# Power_delivery.net
KiCad netlist of a schematic drawn in Altium Designer
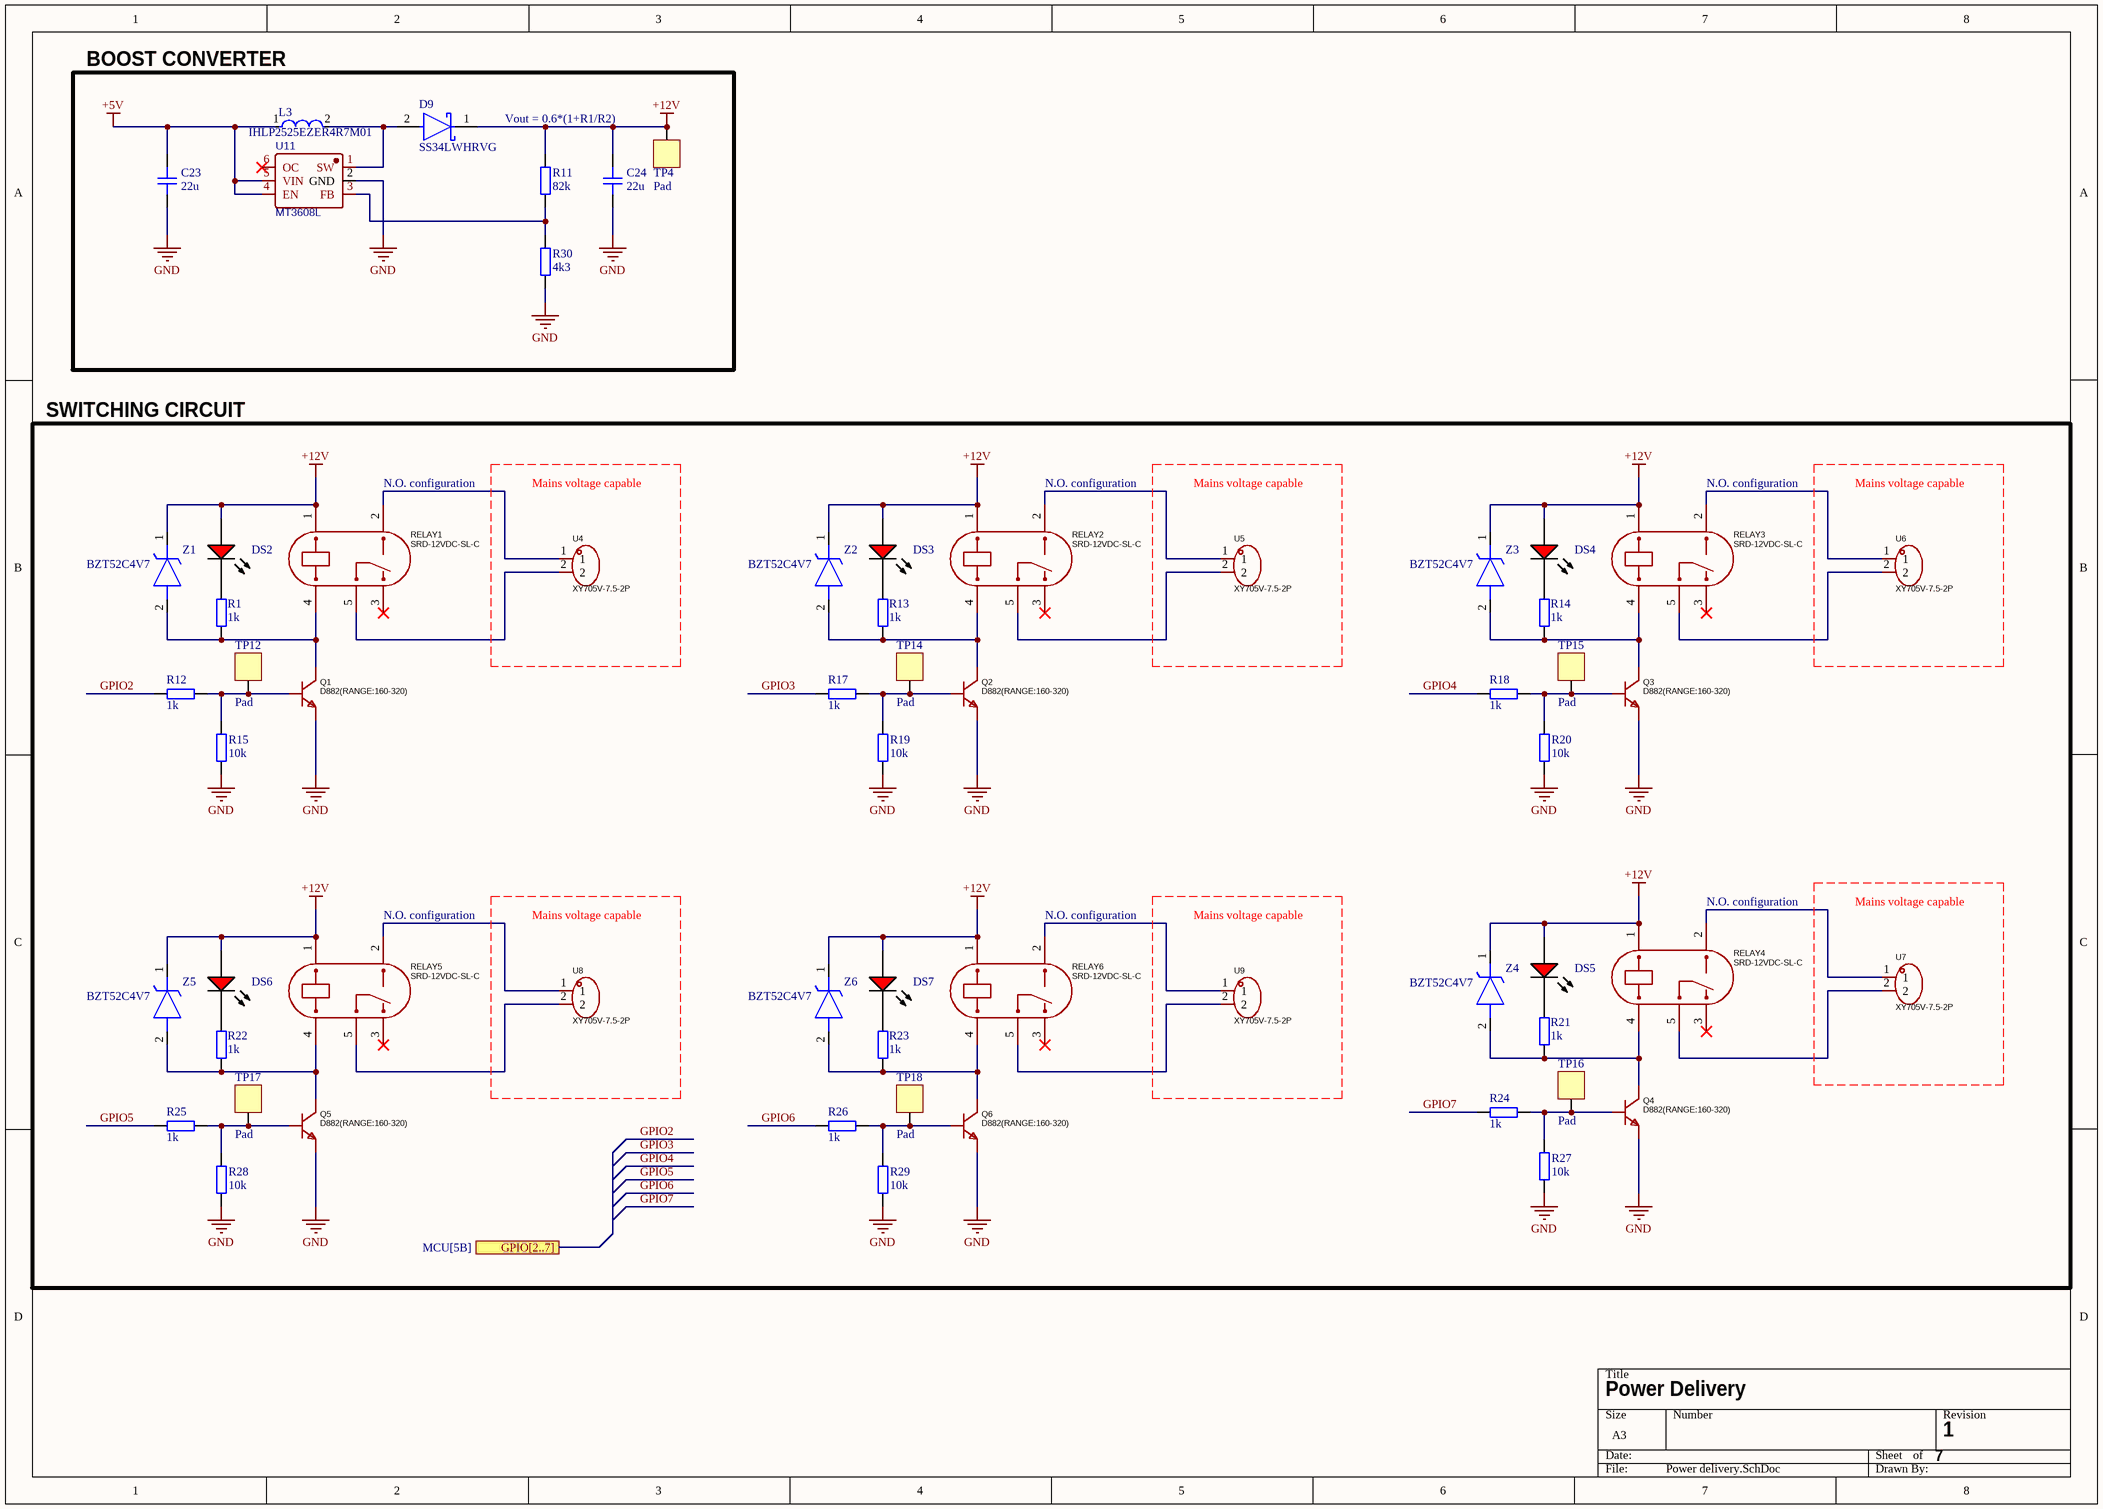
[diagram p0: Power delivery.SchDoc]

(export (version "E")
  (design (tool "Eeschema 10.0.6"))
  (components
    (comp (ref "C23")
      (value "GRM158R61A226ME15D")
      (footprint "CAP_0402")
      (description "Capacitor SMD 0402")
      (fields (field (name "RATING") "22u"))
      (libsource (lib "Schematic-Lib-PhilsLab") (part "CAP_0402"))
    )
    (comp (ref "C24")
      (value "GRM158R61A226ME15D")
      (footprint "CAP_0402")
      (description "Capacitor SMD 0402")
      (fields (field (name "RATING") "22u"))
      (libsource (lib "Schematic-Lib-PhilsLab") (part "CAP_0402"))
    )
    (comp (ref "D9")
      (value "SS34LWHRVG")
      (footprint "FP-SS34LWH-MFG")
      (description "DIODE SCHOTTKY 40V 3A SOD123W")
      (libsource (lib "Altium Content Vault") (part "1d6ec82d83fb6aee721767c19dac4b9"))
    )
    (comp (ref "DS2")
      (value "LTST-C170KRKT")
      (footprint "LTST-C170KRKT_V")
      (description "LED Red, 75 mW, 54 mcd, -55 to 85 degC, 2-Pin SMD, RoHS, Tape and Reel")
      (fields (field (name "MANUFACTURER") "Lite-On"))
      (libsource (lib "Altium Content Vault") (part "LED-RED-AK-2"))
    )
    (comp (ref "DS3")
      (value "LTST-C170KRKT")
      (footprint "LTST-C170KRKT_V")
      (description "LED Red, 75 mW, 54 mcd, -55 to 85 degC, 2-Pin SMD, RoHS, Tape and Reel")
      (fields (field (name "MANUFACTURER") "Lite-On"))
      (libsource (lib "Altium Content Vault") (part "LED-RED-AK-2"))
    )
    (comp (ref "DS4")
      (value "LTST-C170KRKT")
      (footprint "LTST-C170KRKT_V")
      (description "LED Red, 75 mW, 54 mcd, -55 to 85 degC, 2-Pin SMD, RoHS, Tape and Reel")
      (fields (field (name "MANUFACTURER") "Lite-On"))
      (libsource (lib "Altium Content Vault") (part "LED-RED-AK-2"))
    )
    (comp (ref "DS5")
      (value "LTST-C170KRKT")
      (footprint "LTST-C170KRKT_V")
      (description "LED Red, 75 mW, 54 mcd, -55 to 85 degC, 2-Pin SMD, RoHS, Tape and Reel")
      (fields (field (name "MANUFACTURER") "Lite-On"))
      (libsource (lib "Altium Content Vault") (part "LED-RED-AK-2"))
    )
    (comp (ref "DS6")
      (value "LTST-C170KRKT")
      (footprint "LTST-C170KRKT_V")
      (description "LED Red, 75 mW, 54 mcd, -55 to 85 degC, 2-Pin SMD, RoHS, Tape and Reel")
      (fields (field (name "MANUFACTURER") "Lite-On"))
      (libsource (lib "Altium Content Vault") (part "LED-RED-AK-2"))
    )
    (comp (ref "DS7")
      (value "LTST-C170KRKT")
      (footprint "LTST-C170KRKT_V")
      (description "LED Red, 75 mW, 54 mcd, -55 to 85 degC, 2-Pin SMD, RoHS, Tape and Reel")
      (fields (field (name "MANUFACTURER") "Lite-On"))
      (libsource (lib "Altium Content Vault") (part "LED-RED-AK-2"))
    )
    (comp (ref "L3")
      (value "IHLP2525EZER4R7M01")
      (footprint "FP-IHLP-2525EZ-FP_2_413x3-MFG")
      (description "Commercial Inductors, High Saturation Series 4.7uH 6.5A 30.3mΩ 20%")
      (fields (field (name "TOLERANCE") "20%"))
      (libsource (lib "Altium Content Vault") (part "725321dda6339637d4d059423bc1c3c"))
    )
    (comp (ref "Q1")
      (value "D882(RANGE:160-320)")
      (footprint "SOT-89-3_L4.5-W2.5-P1.50-LS4.2-BR")
      (fields (field (name "MANUFACTURER") "CJ(江苏长电/长晶)"))
      (libsource (lib "JLCPCB_parts_library") (part "D882(RANGE{colon}160-320)_C9634"))
    )
    (comp (ref "Q2")
      (value "D882(RANGE:160-320)")
      (footprint "SOT-89-3_L4.5-W2.5-P1.50-LS4.2-BR")
      (fields (field (name "MANUFACTURER") "CJ(江苏长电/长晶)"))
      (libsource (lib "JLCPCB_parts_library") (part "D882(RANGE{colon}160-320)_C9634"))
    )
    (comp (ref "Q3")
      (value "D882(RANGE:160-320)")
      (footprint "SOT-89-3_L4.5-W2.5-P1.50-LS4.2-BR")
      (fields (field (name "MANUFACTURER") "CJ(江苏长电/长晶)"))
      (libsource (lib "JLCPCB_parts_library") (part "D882(RANGE{colon}160-320)_C9634"))
    )
    (comp (ref "Q4")
      (value "D882(RANGE:160-320)")
      (footprint "SOT-89-3_L4.5-W2.5-P1.50-LS4.2-BR")
      (fields (field (name "MANUFACTURER") "CJ(江苏长电/长晶)"))
      (libsource (lib "JLCPCB_parts_library") (part "D882(RANGE{colon}160-320)_C9634"))
    )
    (comp (ref "Q5")
      (value "D882(RANGE:160-320)")
      (footprint "SOT-89-3_L4.5-W2.5-P1.50-LS4.2-BR")
      (fields (field (name "MANUFACTURER") "CJ(江苏长电/长晶)"))
      (libsource (lib "JLCPCB_parts_library") (part "D882(RANGE{colon}160-320)_C9634"))
    )
    (comp (ref "Q6")
      (value "D882(RANGE:160-320)")
      (footprint "SOT-89-3_L4.5-W2.5-P1.50-LS4.2-BR")
      (fields (field (name "MANUFACTURER") "CJ(江苏长电/长晶)"))
      (libsource (lib "JLCPCB_parts_library") (part "D882(RANGE{colon}160-320)_C9634"))
    )
    (comp (ref "R1")
      (value "1k")
      (footprint "RES_1206")
      (description "Resistor SMD 1206 1k 0.5W")
      (fields (field (name "Comment") "RC1206FR-7W1KL"))
      (libsource (lib "Schematic-Lib-PhilsLab") (part "RES_1206"))
    )
    (comp (ref "R11")
      (value "82k")
      (footprint "RES_0402")
      (description "Resistor SMD 0402")
      (fields (field (name "Comment") "0402WGF8202TCE"))
      (libsource (lib "Schematic-Lib-PhilsLab") (part "RES_0402"))
    )
    (comp (ref "R12")
      (value "1k")
      (footprint "RES_1206")
      (description "Resistor SMD 1206 1k 0.5W")
      (fields (field (name "Comment") "RC1206FR-7W1KL"))
      (libsource (lib "Schematic-Lib-PhilsLab") (part "RES_1206"))
    )
    (comp (ref "R13")
      (value "1k")
      (footprint "RES_1206")
      (description "Resistor SMD 1206 1k 0.5W")
      (fields (field (name "Comment") "RC1206FR-7W1KL"))
      (libsource (lib "Schematic-Lib-PhilsLab") (part "RES_1206"))
    )
    (comp (ref "R14")
      (value "1k")
      (footprint "RES_1206")
      (description "Resistor SMD 1206 1k 0.5W")
      (fields (field (name "Comment") "RC1206FR-7W1KL"))
      (libsource (lib "Schematic-Lib-PhilsLab") (part "RES_1206"))
    )
    (comp (ref "R15")
      (value "10k")
      (footprint "RES_1206")
      (description "Resistor SMD 1206 10k 0.25W")
      (fields (field (name "Comment") "1206W4F1002T5E"))
      (libsource (lib "Schematic-Lib-PhilsLab") (part "RES_1206"))
    )
    (comp (ref "R17")
      (value "1k")
      (footprint "RES_1206")
      (description "Resistor SMD 1206 1k 0.5W")
      (fields (field (name "Comment") "RC1206FR-7W1KL"))
      (libsource (lib "Schematic-Lib-PhilsLab") (part "RES_1206"))
    )
    (comp (ref "R18")
      (value "1k")
      (footprint "RES_1206")
      (description "Resistor SMD 1206 1k 0.5W")
      (fields (field (name "Comment") "RC1206FR-7W1KL"))
      (libsource (lib "Schematic-Lib-PhilsLab") (part "RES_1206"))
    )
    (comp (ref "R19")
      (value "10k")
      (footprint "RES_1206")
      (description "Resistor SMD 1206 10k 0.25W")
      (fields (field (name "Comment") "1206W4F1002T5E"))
      (libsource (lib "Schematic-Lib-PhilsLab") (part "RES_1206"))
    )
    (comp (ref "R20")
      (value "10k")
      (footprint "RES_1206")
      (description "Resistor SMD 1206 10k 0.25W")
      (fields (field (name "Comment") "1206W4F1002T5E"))
      (libsource (lib "Schematic-Lib-PhilsLab") (part "RES_1206"))
    )
    (comp (ref "R21")
      (value "1k")
      (footprint "RES_1206")
      (description "Resistor SMD 1206 1k 0.5W")
      (fields (field (name "Comment") "RC1206FR-7W1KL"))
      (libsource (lib "Schematic-Lib-PhilsLab") (part "RES_1206"))
    )
    (comp (ref "R22")
      (value "1k")
      (footprint "RES_1206")
      (description "Resistor SMD 1206 1k 0.5W")
      (fields (field (name "Comment") "RC1206FR-7W1KL"))
      (libsource (lib "Schematic-Lib-PhilsLab") (part "RES_1206"))
    )
    (comp (ref "R23")
      (value "1k")
      (footprint "RES_1206")
      (description "Resistor SMD 1206 1k 0.5W")
      (fields (field (name "Comment") "RC1206FR-7W1KL"))
      (libsource (lib "Schematic-Lib-PhilsLab") (part "RES_1206"))
    )
    (comp (ref "R24")
      (value "1k")
      (footprint "RES_1206")
      (description "Resistor SMD 1206 1k 0.5W")
      (fields (field (name "Comment") "RC1206FR-7W1KL"))
      (libsource (lib "Schematic-Lib-PhilsLab") (part "RES_1206"))
    )
    (comp (ref "R25")
      (value "1k")
      (footprint "RES_1206")
      (description "Resistor SMD 1206 1k 0.5W")
      (fields (field (name "Comment") "RC1206FR-7W1KL"))
      (libsource (lib "Schematic-Lib-PhilsLab") (part "RES_1206"))
    )
    (comp (ref "R26")
      (value "1k")
      (footprint "RES_1206")
      (description "Resistor SMD 1206 1k 0.5W")
      (fields (field (name "Comment") "RC1206FR-7W1KL"))
      (libsource (lib "Schematic-Lib-PhilsLab") (part "RES_1206"))
    )
    (comp (ref "R27")
      (value "10k")
      (footprint "RES_1206")
      (description "Resistor SMD 1206 10k 0.25W")
      (fields (field (name "Comment") "1206W4F1002T5E"))
      (libsource (lib "Schematic-Lib-PhilsLab") (part "RES_1206"))
    )
    (comp (ref "R28")
      (value "10k")
      (footprint "RES_1206")
      (description "Resistor SMD 1206 10k 0.25W")
      (fields (field (name "Comment") "1206W4F1002T5E"))
      (libsource (lib "Schematic-Lib-PhilsLab") (part "RES_1206"))
    )
    (comp (ref "R29")
      (value "10k")
      (footprint "RES_1206")
      (description "Resistor SMD 1206 10k 0.25W")
      (fields (field (name "Comment") "1206W4F1002T5E"))
      (libsource (lib "Schematic-Lib-PhilsLab") (part "RES_1206"))
    )
    (comp (ref "R30")
      (value "4k3")
      (footprint "RES_0402")
      (description "Resistor SMD 0402")
      (fields (field (name "Comment") "RC0402FR-074K3L"))
      (libsource (lib "Schematic-Lib-PhilsLab") (part "RES_0402"))
    )
    (comp (ref "RELAY1")
      (value "SRD-12VDC-SL-C")
      (footprint "RELAY-TH_SRD-XXVDC-XL-C")
      (fields (field (name "MANUFACTURER") "松乐"))
      (libsource (lib "JLCPCB_parts_library") (part "SRD-12VDC-SL-C"))
    )
    (comp (ref "RELAY2")
      (value "SRD-12VDC-SL-C")
      (footprint "RELAY-TH_SRD-XXVDC-XL-C")
      (fields (field (name "MANUFACTURER") "松乐"))
      (libsource (lib "JLCPCB_parts_library") (part "SRD-12VDC-SL-C"))
    )
    (comp (ref "RELAY3")
      (value "SRD-12VDC-SL-C")
      (footprint "RELAY-TH_SRD-XXVDC-XL-C")
      (fields (field (name "MANUFACTURER") "松乐"))
      (libsource (lib "JLCPCB_parts_library") (part "SRD-12VDC-SL-C"))
    )
    (comp (ref "RELAY4")
      (value "SRD-12VDC-SL-C")
      (footprint "RELAY-TH_SRD-XXVDC-XL-C")
      (fields (field (name "MANUFACTURER") "松乐"))
      (libsource (lib "JLCPCB_parts_library") (part "SRD-12VDC-SL-C"))
    )
    (comp (ref "RELAY5")
      (value "SRD-12VDC-SL-C")
      (footprint "RELAY-TH_SRD-XXVDC-XL-C")
      (fields (field (name "MANUFACTURER") "松乐"))
      (libsource (lib "JLCPCB_parts_library") (part "SRD-12VDC-SL-C"))
    )
    (comp (ref "RELAY6")
      (value "SRD-12VDC-SL-C")
      (footprint "RELAY-TH_SRD-XXVDC-XL-C")
      (fields (field (name "MANUFACTURER") "松乐"))
      (libsource (lib "JLCPCB_parts_library") (part "SRD-12VDC-SL-C"))
    )
    (comp (ref "TP4")
      (value "Pad")
      (footprint "PAD_SQ_2MM")
      (description "Test Point Square 2mm")
      (libsource (lib "") (part "PAD_SQ_2MM_1"))
    )
    (comp (ref "TP12")
      (value "Pad")
      (footprint "PAD_SQ_2MM")
      (description "Test Point Square 2mm")
      (libsource (lib "Schematic-Lib-PhilsLab") (part "PAD_SQ_2MM"))
    )
    (comp (ref "TP14")
      (value "Pad")
      (footprint "PAD_SQ_2MM")
      (description "Test Point Square 2mm")
      (libsource (lib "Schematic-Lib-PhilsLab") (part "PAD_SQ_2MM"))
    )
    (comp (ref "TP15")
      (value "Pad")
      (footprint "PAD_SQ_2MM")
      (description "Test Point Square 2mm")
      (libsource (lib "Schematic-Lib-PhilsLab") (part "PAD_SQ_2MM"))
    )
    (comp (ref "TP16")
      (value "Pad")
      (footprint "PAD_SQ_2MM")
      (description "Test Point Square 2mm")
      (libsource (lib "Schematic-Lib-PhilsLab") (part "PAD_SQ_2MM"))
    )
    (comp (ref "TP17")
      (value "Pad")
      (footprint "PAD_SQ_2MM")
      (description "Test Point Square 2mm")
      (libsource (lib "Schematic-Lib-PhilsLab") (part "PAD_SQ_2MM"))
    )
    (comp (ref "TP18")
      (value "Pad")
      (footprint "PAD_SQ_2MM")
      (description "Test Point Square 2mm")
      (libsource (lib "Schematic-Lib-PhilsLab") (part "PAD_SQ_2MM"))
    )
    (comp (ref "U4")
      (value "XY705V-7.5-2P")
      (footprint "CONN-TH_XY705V-7.5-2P")
      (fields (field (name "MANUFACTURER") "XINLAIYA(新莱亚)"))
      (libsource (lib "JLCPCB_parts_library") (part "XY705V-7.5-2P"))
    )
    (comp (ref "U5")
      (value "XY705V-7.5-2P")
      (footprint "CONN-TH_XY705V-7.5-2P")
      (fields (field (name "MANUFACTURER") "XINLAIYA(新莱亚)"))
      (libsource (lib "JLCPCB_parts_library") (part "XY705V-7.5-2P"))
    )
    (comp (ref "U6")
      (value "XY705V-7.5-2P")
      (footprint "CONN-TH_XY705V-7.5-2P")
      (fields (field (name "MANUFACTURER") "XINLAIYA(新莱亚)"))
      (libsource (lib "JLCPCB_parts_library") (part "XY705V-7.5-2P"))
    )
    (comp (ref "U7")
      (value "XY705V-7.5-2P")
      (footprint "CONN-TH_XY705V-7.5-2P")
      (fields (field (name "MANUFACTURER") "XINLAIYA(新莱亚)"))
      (libsource (lib "JLCPCB_parts_library") (part "XY705V-7.5-2P"))
    )
    (comp (ref "U8")
      (value "XY705V-7.5-2P")
      (footprint "CONN-TH_XY705V-7.5-2P")
      (fields (field (name "MANUFACTURER") "XINLAIYA(新莱亚)"))
      (libsource (lib "JLCPCB_parts_library") (part "XY705V-7.5-2P"))
    )
    (comp (ref "U9")
      (value "XY705V-7.5-2P")
      (footprint "CONN-TH_XY705V-7.5-2P")
      (fields (field (name "MANUFACTURER") "XINLAIYA(新莱亚)"))
      (libsource (lib "JLCPCB_parts_library") (part "XY705V-7.5-2P"))
    )
    (comp (ref "U11")
      (value "MT3608L")
      (footprint "SOT-23-6_L2.9-W1.6-P0.95-LS2.8-BL_3")
      (fields (field (name "MANUFACTURER") "西安航天民芯") (field (name "CONTRIBUTOR") "LCSC"))
      (libsource (lib "JLCPCB_parts_library") (part "MT3608L"))
    )
    (comp (ref "Z1")
      (value "BZT52C4V7")
      (footprint "JLCPCB_parts_library:BZT52C4V7")
      (description "Zener Diode")
      (fields (field (name "MOUSER PART NUMBER") "637-BZT52C4V7"))
      (libsource (lib "JLCPCB_parts_library") (part "BZT52C4V7"))
    )
    (comp (ref "Z2")
      (value "BZT52C4V7")
      (footprint "JLCPCB_parts_library:BZT52C4V7")
      (description "Zener Diode")
      (fields (field (name "MOUSER PART NUMBER") "637-BZT52C4V7"))
      (libsource (lib "JLCPCB_parts_library") (part "BZT52C4V7"))
    )
    (comp (ref "Z3")
      (value "BZT52C4V7")
      (footprint "JLCPCB_parts_library:BZT52C4V7")
      (description "Zener Diode")
      (fields (field (name "MOUSER PART NUMBER") "637-BZT52C4V7"))
      (libsource (lib "JLCPCB_parts_library") (part "BZT52C4V7"))
    )
    (comp (ref "Z4")
      (value "BZT52C4V7")
      (footprint "JLCPCB_parts_library:BZT52C4V7")
      (description "Zener Diode")
      (fields (field (name "MOUSER PART NUMBER") "637-BZT52C4V7"))
      (libsource (lib "JLCPCB_parts_library") (part "BZT52C4V7"))
    )
    (comp (ref "Z5")
      (value "BZT52C4V7")
      (footprint "JLCPCB_parts_library:BZT52C4V7")
      (description "Zener Diode")
      (fields (field (name "MOUSER PART NUMBER") "637-BZT52C4V7"))
      (libsource (lib "JLCPCB_parts_library") (part "BZT52C4V7"))
    )
    (comp (ref "Z6")
      (value "BZT52C4V7")
      (footprint "JLCPCB_parts_library:BZT52C4V7")
      (description "Zener Diode")
      (fields (field (name "MOUSER PART NUMBER") "637-BZT52C4V7"))
      (libsource (lib "JLCPCB_parts_library") (part "BZT52C4V7"))
    )
  )
  (nets
    (net (code "1") (name "+5V") (class "Default")
      (node (ref "C23") (pin "2") (pinfunction "2_2") (pintype "passive"))
      (node (ref "L3") (pin "1") (pinfunction "1_1") (pintype "passive"))
      (node (ref "U11") (pin "4") (pinfunction "EN_4") (pintype "passive"))
      (node (ref "U11") (pin "5") (pinfunction "VIN_5") (pintype "passive"))
    )
    (net (code "2") (name "+12V") (class "Default")
      (node (ref "C24") (pin "2") (pinfunction "2_2") (pintype "passive"))
      (node (ref "D9") (pin "1") (pinfunction "C_1") (pintype "passive"))
      (node (ref "DS2") (pin "1") (pinfunction "A_1") (pintype "passive"))
      (node (ref "DS3") (pin "1") (pinfunction "A_1") (pintype "passive"))
      (node (ref "DS4") (pin "1") (pinfunction "A_1") (pintype "passive"))
      (node (ref "DS5") (pin "1") (pinfunction "A_1") (pintype "passive"))
      (node (ref "DS6") (pin "1") (pinfunction "A_1") (pintype "passive"))
      (node (ref "DS7") (pin "1") (pinfunction "A_1") (pintype "passive"))
      (node (ref "R11") (pin "2") (pinfunction "2_2") (pintype "passive"))
      (node (ref "RELAY1") (pin "1") (pinfunction "1_1") (pintype "passive"))
      (node (ref "RELAY2") (pin "1") (pinfunction "1_1") (pintype "passive"))
      (node (ref "RELAY3") (pin "1") (pinfunction "1_1") (pintype "passive"))
      (node (ref "RELAY4") (pin "1") (pinfunction "1_1") (pintype "passive"))
      (node (ref "RELAY5") (pin "1") (pinfunction "1_1") (pintype "passive"))
      (node (ref "RELAY6") (pin "1") (pinfunction "1_1") (pintype "passive"))
      (node (ref "TP4") (pin "1") (pinfunction "1_1") (pintype "passive"))
      (node (ref "Z1") (pin "1") (pinfunction "K_1") (pintype "passive"))
      (node (ref "Z2") (pin "1") (pinfunction "K_1") (pintype "passive"))
      (node (ref "Z3") (pin "1") (pinfunction "K_1") (pintype "passive"))
      (node (ref "Z4") (pin "1") (pinfunction "K_1") (pintype "passive"))
      (node (ref "Z5") (pin "1") (pinfunction "K_1") (pintype "passive"))
      (node (ref "Z6") (pin "1") (pinfunction "K_1") (pintype "passive"))
    )
    (net (code "3") (name "/GPIO2") (class "Default")
      (node (ref "R12") (pin "2") (pinfunction "2_2") (pintype "passive"))
    )
    (net (code "4") (name "/GPIO3") (class "Default")
      (node (ref "R17") (pin "2") (pinfunction "2_2") (pintype "passive"))
    )
    (net (code "5") (name "/GPIO4") (class "Default")
      (node (ref "R18") (pin "2") (pinfunction "2_2") (pintype "passive"))
    )
    (net (code "6") (name "/GPIO5") (class "Default")
      (node (ref "R25") (pin "2") (pinfunction "2_2") (pintype "passive"))
    )
    (net (code "7") (name "/GPIO6") (class "Default")
      (node (ref "R26") (pin "2") (pinfunction "2_2") (pintype "passive"))
    )
    (net (code "8") (name "/GPIO7") (class "Default")
      (node (ref "R24") (pin "2") (pinfunction "2_2") (pintype "passive"))
    )
    (net (code "10") (name "GND") (class "Default")
      (node (ref "C23") (pin "1") (pinfunction "1_1") (pintype "passive"))
      (node (ref "C24") (pin "1") (pinfunction "1_1") (pintype "passive"))
      (node (ref "Q1") (pin "3") (pinfunction "E_3") (pintype "passive"))
      (node (ref "Q2") (pin "3") (pinfunction "E_3") (pintype "passive"))
      (node (ref "Q3") (pin "3") (pinfunction "E_3") (pintype "passive"))
      (node (ref "Q4") (pin "3") (pinfunction "E_3") (pintype "passive"))
      (node (ref "Q5") (pin "3") (pinfunction "E_3") (pintype "passive"))
      (node (ref "Q6") (pin "3") (pinfunction "E_3") (pintype "passive"))
      (node (ref "R15") (pin "1") (pinfunction "1_1") (pintype "passive"))
      (node (ref "R19") (pin "1") (pinfunction "1_1") (pintype "passive"))
      (node (ref "R20") (pin "1") (pinfunction "1_1") (pintype "passive"))
      (node (ref "R27") (pin "1") (pinfunction "1_1") (pintype "passive"))
      (node (ref "R28") (pin "1") (pinfunction "1_1") (pintype "passive"))
      (node (ref "R29") (pin "1") (pinfunction "1_1") (pintype "passive"))
      (node (ref "R30") (pin "1") (pinfunction "1_1") (pintype "passive"))
      (node (ref "U11") (pin "2") (pinfunction "GND_2") (pintype "passive"))
    )
    (net (code "11") (name "Net-(D9-A)") (class "Default")
      (node (ref "D9") (pin "2") (pinfunction "A_2") (pintype "passive"))
      (node (ref "L3") (pin "2") (pinfunction "2_2") (pintype "passive"))
      (node (ref "U11") (pin "1") (pinfunction "SW_1") (pintype "passive"))
    )
    (net (code "12") (name "Net-(DS2-K)") (class "Default")
      (node (ref "DS2") (pin "2") (pinfunction "K_2") (pintype "passive"))
      (node (ref "R1") (pin "1") (pinfunction "1_1") (pintype "passive"))
    )
    (net (code "13") (name "Net-(DS3-K)") (class "Default")
      (node (ref "DS3") (pin "2") (pinfunction "K_2") (pintype "passive"))
      (node (ref "R13") (pin "1") (pinfunction "1_1") (pintype "passive"))
    )
    (net (code "14") (name "Net-(DS4-K)") (class "Default")
      (node (ref "DS4") (pin "2") (pinfunction "K_2") (pintype "passive"))
      (node (ref "R14") (pin "1") (pinfunction "1_1") (pintype "passive"))
    )
    (net (code "15") (name "Net-(DS5-K)") (class "Default")
      (node (ref "DS5") (pin "2") (pinfunction "K_2") (pintype "passive"))
      (node (ref "R21") (pin "1") (pinfunction "1_1") (pintype "passive"))
    )
    (net (code "16") (name "Net-(DS6-K)") (class "Default")
      (node (ref "DS6") (pin "2") (pinfunction "K_2") (pintype "passive"))
      (node (ref "R22") (pin "1") (pinfunction "1_1") (pintype "passive"))
    )
    (net (code "17") (name "Net-(DS7-K)") (class "Default")
      (node (ref "DS7") (pin "2") (pinfunction "K_2") (pintype "passive"))
      (node (ref "R23") (pin "1") (pinfunction "1_1") (pintype "passive"))
    )
    (net (code "18") (name "Net-(Q1-B)") (class "Default")
      (node (ref "Q1") (pin "1") (pinfunction "B_1") (pintype "passive"))
      (node (ref "R12") (pin "1") (pinfunction "1_1") (pintype "passive"))
      (node (ref "R15") (pin "2") (pinfunction "2_2") (pintype "passive"))
      (node (ref "TP12") (pin "1") (pinfunction "1_1") (pintype "passive"))
    )
    (net (code "19") (name "Net-(Q1-C)") (class "Default")
      (node (ref "Q1") (pin "2") (pinfunction "C_2") (pintype "passive"))
      (node (ref "R1") (pin "2") (pinfunction "2_2") (pintype "passive"))
      (node (ref "RELAY1") (pin "4") (pinfunction "4_4") (pintype "passive"))
      (node (ref "Z1") (pin "2") (pinfunction "A_2") (pintype "passive"))
    )
    (net (code "20") (name "Net-(Q2-B)") (class "Default")
      (node (ref "Q2") (pin "1") (pinfunction "B_1") (pintype "passive"))
      (node (ref "R17") (pin "1") (pinfunction "1_1") (pintype "passive"))
      (node (ref "R19") (pin "2") (pinfunction "2_2") (pintype "passive"))
      (node (ref "TP14") (pin "1") (pinfunction "1_1") (pintype "passive"))
    )
    (net (code "21") (name "Net-(Q2-C)") (class "Default")
      (node (ref "Q2") (pin "2") (pinfunction "C_2") (pintype "passive"))
      (node (ref "R13") (pin "2") (pinfunction "2_2") (pintype "passive"))
      (node (ref "RELAY2") (pin "4") (pinfunction "4_4") (pintype "passive"))
      (node (ref "Z2") (pin "2") (pinfunction "A_2") (pintype "passive"))
    )
    (net (code "22") (name "Net-(Q3-B)") (class "Default")
      (node (ref "Q3") (pin "1") (pinfunction "B_1") (pintype "passive"))
      (node (ref "R18") (pin "1") (pinfunction "1_1") (pintype "passive"))
      (node (ref "R20") (pin "2") (pinfunction "2_2") (pintype "passive"))
      (node (ref "TP15") (pin "1") (pinfunction "1_1") (pintype "passive"))
    )
    (net (code "23") (name "Net-(Q3-C)") (class "Default")
      (node (ref "Q3") (pin "2") (pinfunction "C_2") (pintype "passive"))
      (node (ref "R14") (pin "2") (pinfunction "2_2") (pintype "passive"))
      (node (ref "RELAY3") (pin "4") (pinfunction "4_4") (pintype "passive"))
      (node (ref "Z3") (pin "2") (pinfunction "A_2") (pintype "passive"))
    )
    (net (code "24") (name "Net-(Q4-B)") (class "Default")
      (node (ref "Q4") (pin "1") (pinfunction "B_1") (pintype "passive"))
      (node (ref "R24") (pin "1") (pinfunction "1_1") (pintype "passive"))
      (node (ref "R27") (pin "2") (pinfunction "2_2") (pintype "passive"))
      (node (ref "TP16") (pin "1") (pinfunction "1_1") (pintype "passive"))
    )
    (net (code "25") (name "Net-(Q4-C)") (class "Default")
      (node (ref "Q4") (pin "2") (pinfunction "C_2") (pintype "passive"))
      (node (ref "R21") (pin "2") (pinfunction "2_2") (pintype "passive"))
      (node (ref "RELAY4") (pin "4") (pinfunction "4_4") (pintype "passive"))
      (node (ref "Z4") (pin "2") (pinfunction "A_2") (pintype "passive"))
    )
    (net (code "26") (name "Net-(Q5-B)") (class "Default")
      (node (ref "Q5") (pin "1") (pinfunction "B_1") (pintype "passive"))
      (node (ref "R25") (pin "1") (pinfunction "1_1") (pintype "passive"))
      (node (ref "R28") (pin "2") (pinfunction "2_2") (pintype "passive"))
      (node (ref "TP17") (pin "1") (pinfunction "1_1") (pintype "passive"))
    )
    (net (code "27") (name "Net-(Q5-C)") (class "Default")
      (node (ref "Q5") (pin "2") (pinfunction "C_2") (pintype "passive"))
      (node (ref "R22") (pin "2") (pinfunction "2_2") (pintype "passive"))
      (node (ref "RELAY5") (pin "4") (pinfunction "4_4") (pintype "passive"))
      (node (ref "Z5") (pin "2") (pinfunction "A_2") (pintype "passive"))
    )
    (net (code "28") (name "Net-(Q6-B)") (class "Default")
      (node (ref "Q6") (pin "1") (pinfunction "B_1") (pintype "passive"))
      (node (ref "R26") (pin "1") (pinfunction "1_1") (pintype "passive"))
      (node (ref "R29") (pin "2") (pinfunction "2_2") (pintype "passive"))
      (node (ref "TP18") (pin "1") (pinfunction "1_1") (pintype "passive"))
    )
    (net (code "29") (name "Net-(Q6-C)") (class "Default")
      (node (ref "Q6") (pin "2") (pinfunction "C_2") (pintype "passive"))
      (node (ref "R23") (pin "2") (pinfunction "2_2") (pintype "passive"))
      (node (ref "RELAY6") (pin "4") (pinfunction "4_4") (pintype "passive"))
      (node (ref "Z6") (pin "2") (pinfunction "A_2") (pintype "passive"))
    )
    (net (code "30") (name "Net-(RELAY1-Pad2)") (class "Default")
      (node (ref "RELAY1") (pin "2") (pinfunction "2_2") (pintype "passive"))
      (node (ref "U4") (pin "1") (pinfunction "1_1") (pintype "passive"))
    )
    (net (code "31") (name "Net-(RELAY1-Pad5)") (class "Default")
      (node (ref "RELAY1") (pin "5") (pinfunction "5_5") (pintype "passive"))
      (node (ref "U4") (pin "2") (pinfunction "2_2") (pintype "passive"))
    )
    (net (code "32") (name "Net-(RELAY2-Pad2)") (class "Default")
      (node (ref "RELAY2") (pin "2") (pinfunction "2_2") (pintype "passive"))
      (node (ref "U5") (pin "1") (pinfunction "1_1") (pintype "passive"))
    )
    (net (code "33") (name "Net-(RELAY2-Pad5)") (class "Default")
      (node (ref "RELAY2") (pin "5") (pinfunction "5_5") (pintype "passive"))
      (node (ref "U5") (pin "2") (pinfunction "2_2") (pintype "passive"))
    )
    (net (code "34") (name "Net-(RELAY3-Pad2)") (class "Default")
      (node (ref "RELAY3") (pin "2") (pinfunction "2_2") (pintype "passive"))
      (node (ref "U6") (pin "1") (pinfunction "1_1") (pintype "passive"))
    )
    (net (code "35") (name "Net-(RELAY3-Pad5)") (class "Default")
      (node (ref "RELAY3") (pin "5") (pinfunction "5_5") (pintype "passive"))
      (node (ref "U6") (pin "2") (pinfunction "2_2") (pintype "passive"))
    )
    (net (code "36") (name "Net-(RELAY4-Pad2)") (class "Default")
      (node (ref "RELAY4") (pin "2") (pinfunction "2_2") (pintype "passive"))
      (node (ref "U7") (pin "1") (pinfunction "1_1") (pintype "passive"))
    )
    (net (code "37") (name "Net-(RELAY4-Pad5)") (class "Default")
      (node (ref "RELAY4") (pin "5") (pinfunction "5_5") (pintype "passive"))
      (node (ref "U7") (pin "2") (pinfunction "2_2") (pintype "passive"))
    )
    (net (code "38") (name "Net-(RELAY5-Pad2)") (class "Default")
      (node (ref "RELAY5") (pin "2") (pinfunction "2_2") (pintype "passive"))
      (node (ref "U8") (pin "1") (pinfunction "1_1") (pintype "passive"))
    )
    (net (code "39") (name "Net-(RELAY5-Pad5)") (class "Default")
      (node (ref "RELAY5") (pin "5") (pinfunction "5_5") (pintype "passive"))
      (node (ref "U8") (pin "2") (pinfunction "2_2") (pintype "passive"))
    )
    (net (code "40") (name "Net-(RELAY6-Pad2)") (class "Default")
      (node (ref "RELAY6") (pin "2") (pinfunction "2_2") (pintype "passive"))
      (node (ref "U9") (pin "1") (pinfunction "1_1") (pintype "passive"))
    )
    (net (code "41") (name "Net-(RELAY6-Pad5)") (class "Default")
      (node (ref "RELAY6") (pin "5") (pinfunction "5_5") (pintype "passive"))
      (node (ref "U9") (pin "2") (pinfunction "2_2") (pintype "passive"))
    )
    (net (code "42") (name "Net-(U11-FB)") (class "Default")
      (node (ref "R11") (pin "1") (pinfunction "1_1") (pintype "passive"))
      (node (ref "R30") (pin "2") (pinfunction "2_2") (pintype "passive"))
      (node (ref "U11") (pin "3") (pinfunction "FB_3") (pintype "passive"))
    )
    (net (code "43") (name "unconnected-(RELAY1-Pad3)") (class "Default")
      (node (ref "RELAY1") (pin "3") (pinfunction "3_3") (pintype "passive+no_connect"))
    )
    (net (code "44") (name "unconnected-(RELAY2-Pad3)") (class "Default")
      (node (ref "RELAY2") (pin "3") (pinfunction "3_3") (pintype "passive+no_connect"))
    )
    (net (code "45") (name "unconnected-(RELAY3-Pad3)") (class "Default")
      (node (ref "RELAY3") (pin "3") (pinfunction "3_3") (pintype "passive+no_connect"))
    )
    (net (code "46") (name "unconnected-(RELAY4-Pad3)") (class "Default")
      (node (ref "RELAY4") (pin "3") (pinfunction "3_3") (pintype "passive+no_connect"))
    )
    (net (code "47") (name "unconnected-(RELAY5-Pad3)") (class "Default")
      (node (ref "RELAY5") (pin "3") (pinfunction "3_3") (pintype "passive+no_connect"))
    )
    (net (code "48") (name "unconnected-(RELAY6-Pad3)") (class "Default")
      (node (ref "RELAY6") (pin "3") (pinfunction "3_3") (pintype "passive+no_connect"))
    )
    (net (code "49") (name "unconnected-(U11-OC-Pad6)") (class "Default")
      (node (ref "U11") (pin "6") (pinfunction "OC_6") (pintype "passive+no_connect"))
    )
  )
)
